# EcobitNRF9160.net
KiCad netlist of a schematic drawn in EAGLE
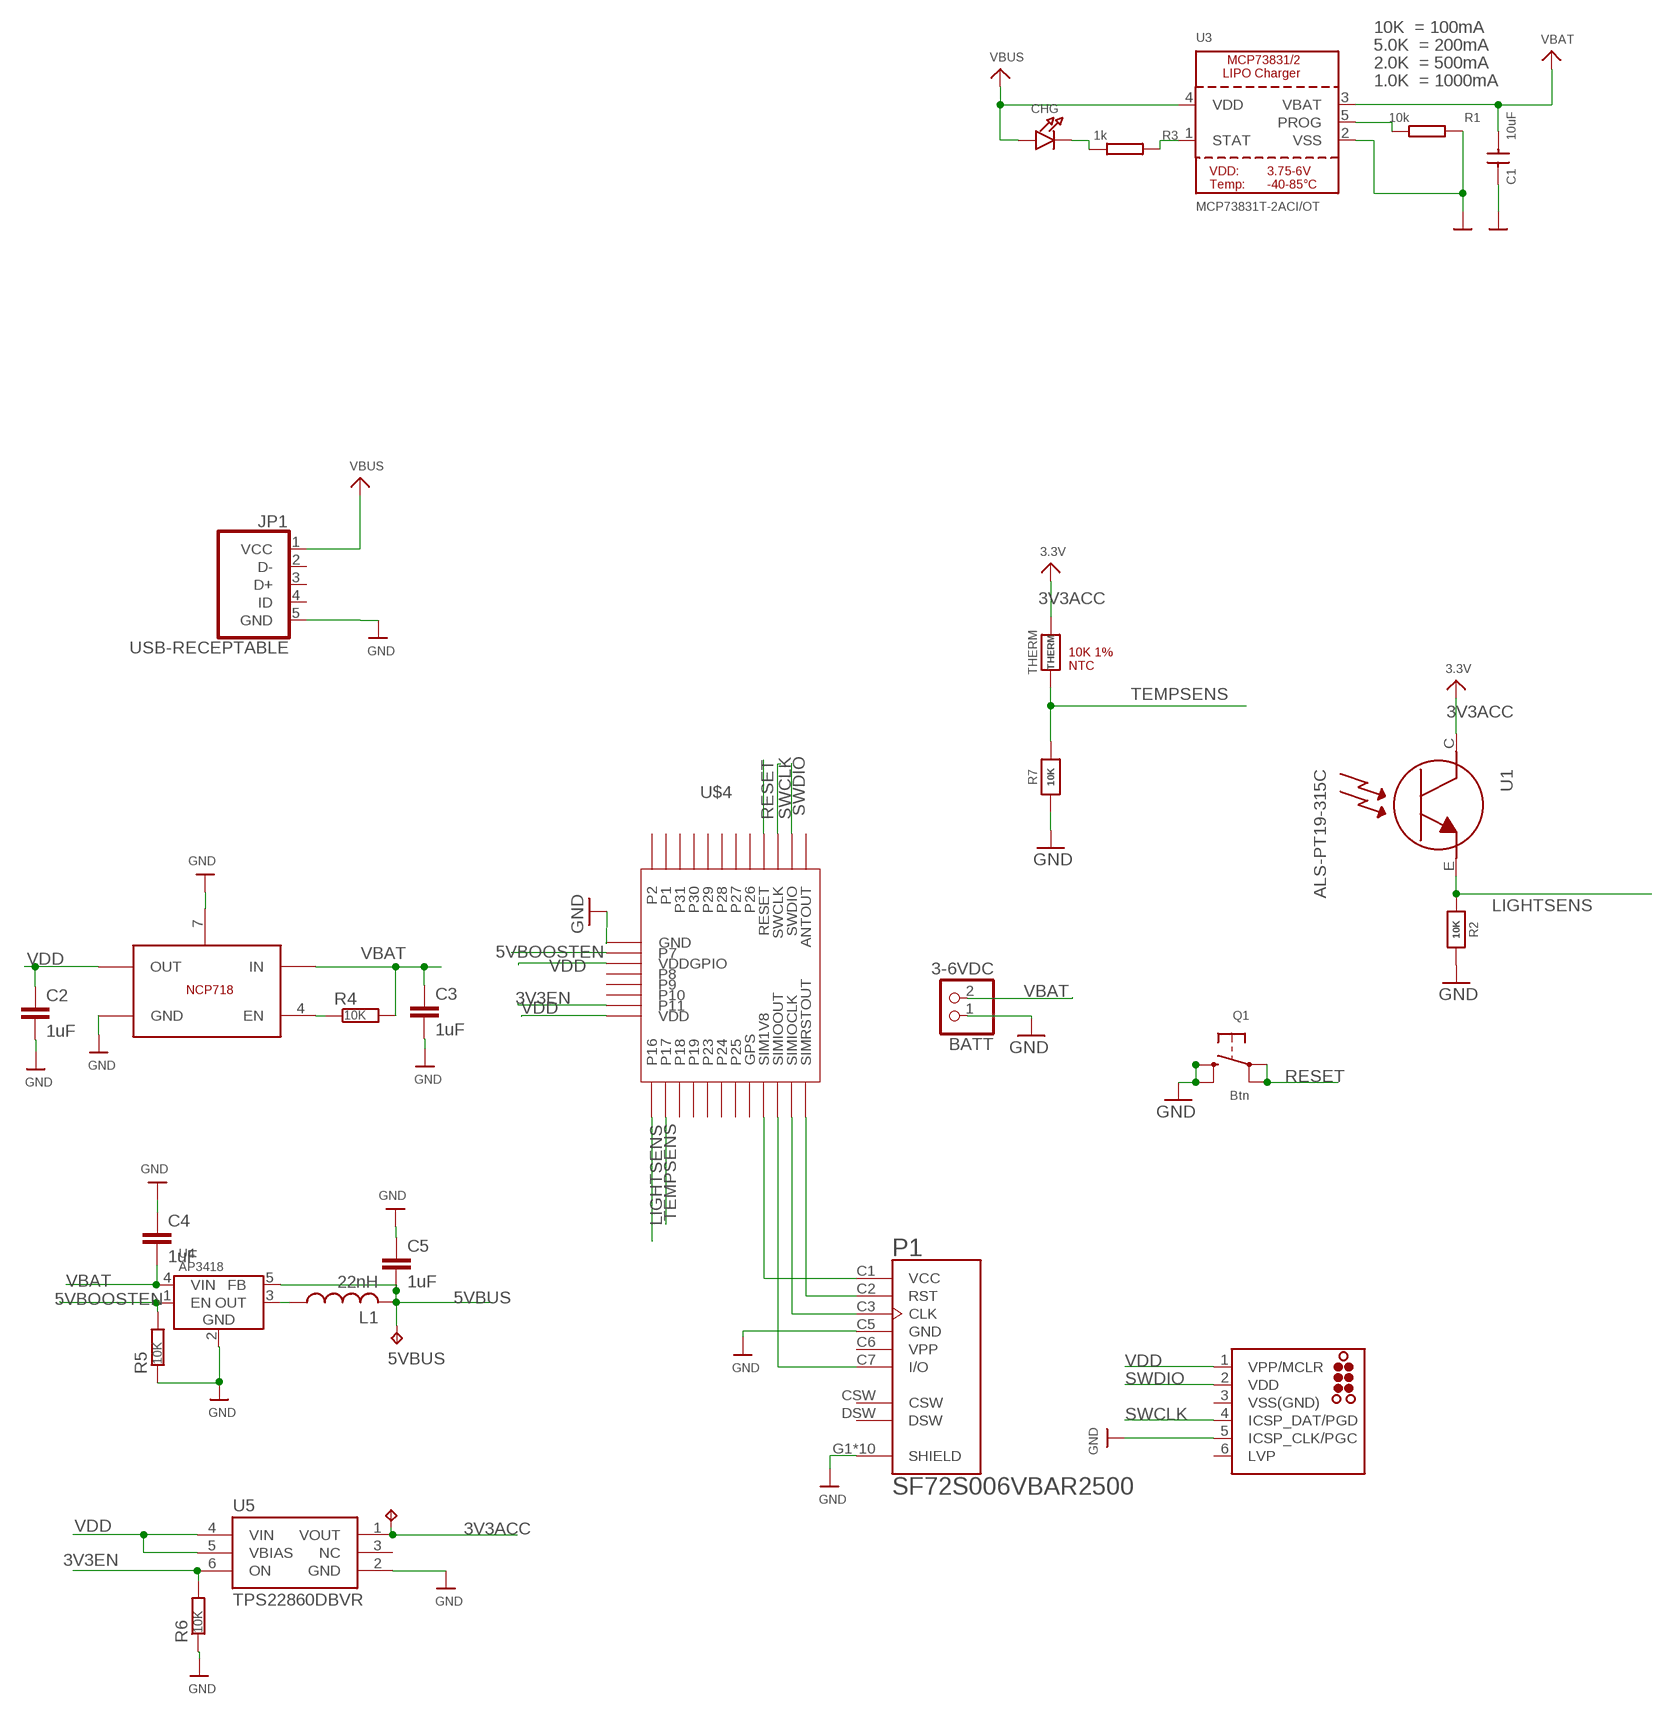
[diagram p0: schematic, sheet 1]

(export (version "E")
  (design (tool "Eeschema 10.0.6"))
  (components
    (comp (ref "5VBUS")
      (value "TPTP15R")
      (footprint "eagle-import:TP15R")
      (libsource (lib "eagle-import") (part "TPTP15R"))
    )
    (comp (ref "5VBUS1")
      (value "TPTP15R")
      (footprint "eagle-import:TP15R")
      (libsource (lib "eagle-import") (part "TPTP15R"))
    )
    (comp (ref "BATT")
      (value "3-6VDC")
      (footprint "eagle-import:JSTPH2")
      (libsource (lib "eagle-import") (part "CON_JST_PH_2PIN"))
    )
    (comp (ref "C1")
      (value "10uF")
      (footprint "eagle-import:C-0402")
      (libsource (lib "eagle-import") (part "CAP0402"))
    )
    (comp (ref "C2")
      (value "1uF")
      (footprint "eagle-import:RESC0402_N")
      (libsource (lib "eagle-import") (part "CAPACITOR_0402_N"))
    )
    (comp (ref "C3")
      (value "1uF")
      (footprint "eagle-import:RESC0402_N")
      (libsource (lib "eagle-import") (part "CAPACITOR_0402_N"))
    )
    (comp (ref "C4")
      (value "1uF")
      (footprint "eagle-import:RESC0402_N")
      (libsource (lib "eagle-import") (part "CAPACITOR_0402_N"))
    )
    (comp (ref "C5")
      (value "1uF")
      (footprint "eagle-import:RESC0402_N")
      (libsource (lib "eagle-import") (part "CAPACITOR_0402_N"))
    )
    (comp (ref "CHG")
      (value "LED0805_NOOUTLINE")
      (footprint "eagle-import:CHIPLED_0805_NOOUTLINE")
      (libsource (lib "eagle-import") (part "LED0805_NOOUTLINE"))
    )
    (comp (ref "J2")
      (value "TC2030-MCP-NL")
      (footprint "eagle-import:TC2030-MCP-NL")
      (libsource (lib "eagle-import") (part "TC2030-MCP-NL"))
    )
    (comp (ref "JP1")
      (value "USB-RECEPTABLE")
      (footprint "eagle-import:FCI-10103594-0001LF")
      (libsource (lib "eagle-import") (part "USB-RECEPTABLE"))
    )
    (comp (ref "L1")
      (value "22nH")
      (footprint "eagle-import:RESC0603_N")
      (libsource (lib "eagle-import") (part "INDUCTOR_0603_N"))
    )
    (comp (ref "P1")
      (value "SF72S006VBAR2500")
      (footprint "eagle-import:JAE_SF72S006VBAR2500")
      (fields (field (name "MF") "JAE Electronics"))
      (libsource (lib "eagle-import") (part "SF72S006VBAR2500"))
    )
    (comp (ref "Q1")
      (value "Btn")
      (footprint "eagle-import:BTN_KMR2_4.6X2.8")
      (libsource (lib "eagle-import") (part "SWITCH_TACT_SMT4.6X2.8"))
    )
    (comp (ref "R1")
      (value "10k")
      (footprint "eagle-import:R0402")
      (libsource (lib "eagle-import") (part "RESR0402"))
    )
    (comp (ref "R2")
      (value "10K")
      (footprint "eagle-import:0603-NO")
      (libsource (lib "eagle-import") (part "RESISTOR_0603_NOOUT"))
    )
    (comp (ref "R3")
      (value "1k")
      (footprint "eagle-import:R0402")
      (libsource (lib "eagle-import") (part "RESR0402"))
    )
    (comp (ref "R4")
      (value "10K")
      (footprint "eagle-import:RESC0402_N")
      (libsource (lib "eagle-import") (part "RESISTOR_0402_N"))
    )
    (comp (ref "R5")
      (value "10K")
      (footprint "eagle-import:RESC0402_N")
      (libsource (lib "eagle-import") (part "RESISTOR_0402_N"))
    )
    (comp (ref "R6")
      (value "10K")
      (footprint "eagle-import:RESC0402_N")
      (libsource (lib "eagle-import") (part "RESISTOR_0402_N"))
    )
    (comp (ref "R7")
      (value "10K")
      (footprint "eagle-import:0603-NO")
      (libsource (lib "eagle-import") (part "RESISTOR_0603_NOOUT"))
    )
    (comp (ref "THERM")
      (value "THERM")
      (footprint "eagle-import:_0402")
      (libsource (lib "eagle-import") (part "RESISTOR_0402"))
    )
    (comp (ref "U$4")
      (value "NRF9160MODULE")
      (footprint "eagle-import:NRF9160MODULE")
      (libsource (lib "eagle-import") (part "NRF9160MODULE"))
    )
    (comp (ref "U1")
      (value "ALS-PT19-315C")
      (footprint "eagle-import:ALS-PT19-315C")
      (libsource (lib "eagle-import") (part "LIGHT_ALS-PT19-315C"))
    )
    (comp (ref "U2")
      (value "NCP718")
      (footprint "eagle-import:NCP718-WDFN6")
      (libsource (lib "eagle-import") (part "NCP718"))
    )
    (comp (ref "U3")
      (value "MCP73831T-2ACI/OT")
      (footprint "eagle-import:SOT23-5")
      (libsource (lib "eagle-import") (part "MCP73831/2"))
    )
    (comp (ref "U4")
      (value "AP3418")
      (footprint "eagle-import:SOT25")
      (libsource (lib "eagle-import") (part "AP3418"))
    )
    (comp (ref "U5")
      (value "TPS22860DBVR")
      (footprint "eagle-import:R-PDSO-G6")
      (libsource (lib "eagle-import") (part "TPS22860DBVR"))
    )
  )
  (nets
    (net (code "1") (name "/3V3EN") (class "Default")
      (node (ref "R6") (pin "2") (pinfunction "2_2") (pintype "passive"))
      (node (ref "U$4") (pin "P11") (pinfunction "P11_P11") (pintype "bidirectional"))
      (node (ref "U5") (pin "6") (pinfunction "ON_6") (pintype "input"))
    )
    (net (code "2") (name "/5VBOOSTEN") (class "Default")
      (node (ref "R5") (pin "2") (pinfunction "2_2") (pintype "passive"))
      (node (ref "U$4") (pin "P7") (pinfunction "P7_P7") (pintype "bidirectional"))
      (node (ref "U4") (pin "1") (pinfunction "EN_1") (pintype "bidirectional"))
    )
    (net (code "3") (name "/5VBUS") (class "Default")
      (node (ref "5VBUS") (pin "TP") (pinfunction "TP_TP") (pintype "input"))
      (node (ref "C5") (pin "2") (pinfunction "2_2") (pintype "passive"))
      (node (ref "L1") (pin "2") (pinfunction "2_2") (pintype "passive"))
      (node (ref "U4") (pin "5") (pinfunction "FB_5") (pintype "bidirectional"))
    )
    (net (code "4") (name "/LIGHTSENS") (class "Default")
      (node (ref "R2") (pin "2") (pinfunction "2_2") (pintype "passive"))
      (node (ref "U$4") (pin "P16") (pinfunction "P16_P16") (pintype "bidirectional"))
      (node (ref "U1") (pin "E") (pinfunction "E_E") (pintype "bidirectional"))
    )
    (net (code "5") (name "/RESET") (class "Default")
      (node (ref "Q1") (pin "A") (pinfunction "P_A") (pintype "passive"))
      (node (ref "Q1") (pin "A'") (pinfunction "P1_A'") (pintype "passive"))
      (node (ref "U$4") (pin "RESET") (pinfunction "RESET_RESET") (pintype "bidirectional"))
    )
    (net (code "6") (name "/SWCLK") (class "Default")
      (node (ref "J2") (pin "4") (pinfunction "ICSP_DAT/PGD_4") (pintype "bidirectional"))
      (node (ref "U$4") (pin "SWCLK") (pinfunction "SWCLK_SWCLK") (pintype "bidirectional"))
    )
    (net (code "7") (name "/SWDIO") (class "Default")
      (node (ref "J2") (pin "2") (pinfunction "VDD_2") (pintype "power_in"))
      (node (ref "U$4") (pin "SWDIO") (pinfunction "SWDIO_SWDIO") (pintype "bidirectional"))
    )
    (net (code "8") (name "/TEMPSENS") (class "Default")
      (node (ref "R7") (pin "2") (pinfunction "2_2") (pintype "passive"))
      (node (ref "THERM") (pin "1") (pinfunction "1_1") (pintype "passive"))
      (node (ref "U$4") (pin "P17") (pinfunction "P17_P17") (pintype "bidirectional"))
    )
    (net (code "9") (name "/VDD") (class "Default")
      (node (ref "C2") (pin "1") (pinfunction "1_1") (pintype "passive"))
      (node (ref "J2") (pin "1") (pinfunction "VPP/MCLR_1") (pintype "passive"))
      (node (ref "U$4") (pin "VDD") (pinfunction "VDD_VDD") (pintype "bidirectional"))
      (node (ref "U$4") (pin "VDDGPIO") (pinfunction "VDDGPIO_VDDGPIO") (pintype "bidirectional"))
      (node (ref "U2") (pin "1") (pinfunction "OUT_1") (pintype "power_in"))
      (node (ref "U5") (pin "4") (pinfunction "VIN_4") (pintype "power_in"))
      (node (ref "U5") (pin "5") (pinfunction "VBIAS_5") (pintype "power_in"))
    )
    (net (code "10") (name "/VPP") (class "Default")
      (node (ref "P1") (pin "C6") (pinfunction "VPP_C6") (pintype "power_in"))
    )
    (net (code "11") (name "/VSS(GND)") (class "Default")
      (node (ref "J2") (pin "3") (pinfunction "VSS(GND)_3") (pintype "power_in"))
    )
    (net (code "12") (name "3.3V") (class "Default")
      (node (ref "5VBUS1") (pin "TP") (pinfunction "TP_TP") (pintype "input"))
      (node (ref "THERM") (pin "2") (pinfunction "2_2") (pintype "passive"))
      (node (ref "U1") (pin "C") (pinfunction "C_C") (pintype "bidirectional"))
      (node (ref "U5") (pin "1") (pinfunction "VOUT_1") (pintype "power_in"))
    )
    (net (code "13") (name "GND") (class "Default")
      (node (ref "BATT") (pin "1") (pinfunction "1_1") (pintype "passive"))
      (node (ref "C1") (pin "2") (pinfunction "2_2") (pintype "bidirectional"))
      (node (ref "C2") (pin "2") (pinfunction "2_2") (pintype "passive"))
      (node (ref "C3") (pin "2") (pinfunction "2_2") (pintype "passive"))
      (node (ref "C4") (pin "1") (pinfunction "1_1") (pintype "passive"))
      (node (ref "C5") (pin "1") (pinfunction "1_1") (pintype "passive"))
      (node (ref "J2") (pin "5") (pinfunction "ICSP_CLK/PGC_5") (pintype "output"))
      (node (ref "JP1") (pin "5") (pinfunction "GND_5") (pintype "bidirectional"))
      (node (ref "P1") (pin "C5") (pinfunction "GND_C5") (pintype "power_in"))
      (node (ref "P1") (pin "G1") (pinfunction "SHIELD_G1") (pintype "passive"))
      (node (ref "P1") (pin "G10") (pinfunction "SHIELD_G10") (pintype "passive"))
      (node (ref "P1") (pin "G2") (pinfunction "SHIELD_G2") (pintype "passive"))
      (node (ref "P1") (pin "G3") (pinfunction "SHIELD_G3") (pintype "passive"))
      (node (ref "P1") (pin "G4") (pinfunction "SHIELD_G4") (pintype "passive"))
      (node (ref "P1") (pin "G5") (pinfunction "SHIELD_G5") (pintype "passive"))
      (node (ref "P1") (pin "G6") (pinfunction "SHIELD_G6") (pintype "passive"))
      (node (ref "P1") (pin "G7") (pinfunction "SHIELD_G7") (pintype "passive"))
      (node (ref "P1") (pin "G8") (pinfunction "SHIELD_G8") (pintype "passive"))
      (node (ref "P1") (pin "G9") (pinfunction "SHIELD_G9") (pintype "passive"))
      (node (ref "Q1") (pin "B") (pinfunction "S_B") (pintype "passive"))
      (node (ref "Q1") (pin "B'") (pinfunction "S1_B'") (pintype "passive"))
      (node (ref "R1") (pin "1") (pinfunction "1_1") (pintype "bidirectional"))
      (node (ref "R2") (pin "1") (pinfunction "1_1") (pintype "passive"))
      (node (ref "R5") (pin "1") (pinfunction "1_1") (pintype "passive"))
      (node (ref "R6") (pin "1") (pinfunction "1_1") (pintype "passive"))
      (node (ref "R7") (pin "1") (pinfunction "1_1") (pintype "passive"))
      (node (ref "U$4") (pin "GND") (pinfunction "GND_GND") (pintype "bidirectional"))
      (node (ref "U2") (pin "3") (pinfunction "GND_3") (pintype "power_in"))
      (node (ref "U2") (pin "7") (pinfunction "GND_7") (pintype "power_in"))
      (node (ref "U3") (pin "2") (pinfunction "VSS_2") (pintype "power_in"))
      (node (ref "U4") (pin "2") (pinfunction "GND_2") (pintype "bidirectional"))
      (node (ref "U5") (pin "2") (pinfunction "GND_2") (pintype "power_in"))
    )
    (net (code "14") (name "Net-(CHG-PadC)") (class "Default")
      (node (ref "CHG") (pin "C") (pinfunction "C_C") (pintype "passive"))
      (node (ref "R3") (pin "2") (pinfunction "2_2") (pintype "bidirectional"))
    )
    (net (code "15") (name "Net-(P1-CLK)") (class "Default")
      (node (ref "P1") (pin "C3") (pinfunction "CLK_C3") (pintype "bidirectional"))
      (node (ref "U$4") (pin "SIMCLKOUT") (pinfunction "SIMIOCLK_SIMCLKOUT") (pintype "bidirectional"))
    )
    (net (code "16") (name "Net-(P1-I{slash}O)") (class "Default")
      (node (ref "P1") (pin "C7") (pinfunction "I/O_C7") (pintype "bidirectional"))
      (node (ref "U$4") (pin "SIMIOOUT") (pinfunction "SIMIOOUT_SIMIOOUT") (pintype "bidirectional"))
    )
    (net (code "17") (name "Net-(P1-RST)") (class "Default")
      (node (ref "P1") (pin "C2") (pinfunction "RST_C2") (pintype "bidirectional"))
      (node (ref "U$4") (pin "SIMRSTOUT") (pinfunction "SIMRSTOUT_SIMRSTOUT") (pintype "bidirectional"))
    )
    (net (code "18") (name "Net-(P1-VCC)") (class "Default")
      (node (ref "P1") (pin "C1") (pinfunction "VCC_C1") (pintype "power_in"))
      (node (ref "U$4") (pin "SIM1V8") (pinfunction "SIM1V8_SIM1V8") (pintype "bidirectional"))
    )
    (net (code "19") (name "Net-(U2-EN)") (class "Default")
      (node (ref "R4") (pin "1") (pinfunction "1_1") (pintype "passive"))
      (node (ref "U2") (pin "4") (pinfunction "EN_4") (pintype "bidirectional"))
    )
    (net (code "20") (name "Net-(U3-PROG)") (class "Default")
      (node (ref "R1") (pin "2") (pinfunction "2_2") (pintype "bidirectional"))
      (node (ref "U3") (pin "5") (pinfunction "PROG_5") (pintype "input"))
    )
    (net (code "21") (name "Net-(U3-STAT)") (class "Default")
      (node (ref "R3") (pin "1") (pinfunction "1_1") (pintype "bidirectional"))
      (node (ref "U3") (pin "1") (pinfunction "STAT_1") (pintype "output"))
    )
    (net (code "22") (name "Net-(U4-OUT)") (class "Default")
      (node (ref "L1") (pin "1") (pinfunction "1_1") (pintype "passive"))
      (node (ref "U4") (pin "3") (pinfunction "OUT_3") (pintype "bidirectional"))
    )
    (net (code "23") (name "VBAT") (class "Default")
      (node (ref "BATT") (pin "2") (pinfunction "2_2") (pintype "passive"))
      (node (ref "C1") (pin "1") (pinfunction "1_1") (pintype "bidirectional"))
      (node (ref "C3") (pin "1") (pinfunction "1_1") (pintype "passive"))
      (node (ref "C4") (pin "2") (pinfunction "2_2") (pintype "passive"))
      (node (ref "R4") (pin "2") (pinfunction "2_2") (pintype "passive"))
      (node (ref "U2") (pin "6") (pinfunction "IN_6") (pintype "power_in"))
      (node (ref "U3") (pin "3") (pinfunction "VBAT_3") (pintype "power_in"))
      (node (ref "U4") (pin "4") (pinfunction "VIN_4") (pintype "bidirectional"))
    )
    (net (code "24") (name "VBUS") (class "Default")
      (node (ref "CHG") (pin "A") (pinfunction "A_A") (pintype "passive"))
      (node (ref "JP1") (pin "1") (pinfunction "VCC_1") (pintype "bidirectional"))
      (node (ref "U3") (pin "4") (pinfunction "VDD_4") (pintype "power_in"))
    )
    (net (code "25") (name "unconnected-(J2-LVP-Pad6)") (class "Default")
      (node (ref "J2") (pin "6") (pinfunction "LVP_6") (pintype "bidirectional"))
    )
    (net (code "26") (name "unconnected-(JP1-D+-Pad3)") (class "Default")
      (node (ref "JP1") (pin "3") (pinfunction "D+_3") (pintype "bidirectional"))
    )
    (net (code "27") (name "unconnected-(JP1-D--Pad2)") (class "Default")
      (node (ref "JP1") (pin "2") (pinfunction "D-_2") (pintype "bidirectional"))
    )
    (net (code "28") (name "unconnected-(JP1-ID-Pad4)") (class "Default")
      (node (ref "JP1") (pin "4") (pinfunction "ID_4") (pintype "bidirectional"))
    )
    (net (code "29") (name "unconnected-(P1-PadCSW)") (class "Default")
      (node (ref "P1") (pin "CSW") (pinfunction "CSW_CSW") (pintype "bidirectional"))
    )
    (net (code "30") (name "unconnected-(P1-PadDSW)") (class "Default")
      (node (ref "P1") (pin "DSW") (pinfunction "DSW_DSW") (pintype "bidirectional"))
    )
    (net (code "31") (name "unconnected-(U$4-PadANTOUT)") (class "Default")
      (node (ref "U$4") (pin "ANTOUT") (pinfunction "ANTOUT_ANTOUT") (pintype "bidirectional"))
    )
    (net (code "32") (name "unconnected-(U$4-PadGPS)") (class "Default")
      (node (ref "U$4") (pin "GPS") (pinfunction "GPS_GPS") (pintype "bidirectional"))
    )
    (net (code "33") (name "unconnected-(U$4-PadP1)") (class "Default")
      (node (ref "U$4") (pin "P1") (pinfunction "P1_P1") (pintype "bidirectional"))
    )
    (net (code "34") (name "unconnected-(U$4-PadP2)") (class "Default")
      (node (ref "U$4") (pin "P2") (pinfunction "P2_P2") (pintype "bidirectional"))
    )
    (net (code "35") (name "unconnected-(U$4-PadP8)") (class "Default")
      (node (ref "U$4") (pin "P8") (pinfunction "P8_P8") (pintype "bidirectional"))
    )
    (net (code "36") (name "unconnected-(U$4-PadP9)") (class "Default")
      (node (ref "U$4") (pin "P9") (pinfunction "P9_P9") (pintype "bidirectional"))
    )
    (net (code "37") (name "unconnected-(U$4-PadP10)") (class "Default")
      (node (ref "U$4") (pin "P10") (pinfunction "P10_P10") (pintype "bidirectional"))
    )
    (net (code "38") (name "unconnected-(U$4-PadP18)") (class "Default")
      (node (ref "U$4") (pin "P18") (pinfunction "P18_P18") (pintype "bidirectional"))
    )
    (net (code "39") (name "unconnected-(U$4-PadP19)") (class "Default")
      (node (ref "U$4") (pin "P19") (pinfunction "P19_P19") (pintype "bidirectional"))
    )
    (net (code "40") (name "unconnected-(U$4-PadP23)") (class "Default")
      (node (ref "U$4") (pin "P23") (pinfunction "P23_P23") (pintype "bidirectional"))
    )
    (net (code "41") (name "unconnected-(U$4-PadP24)") (class "Default")
      (node (ref "U$4") (pin "P24") (pinfunction "P24_P24") (pintype "bidirectional"))
    )
    (net (code "42") (name "unconnected-(U$4-PadP25)") (class "Default")
      (node (ref "U$4") (pin "P25") (pinfunction "P25_P25") (pintype "bidirectional"))
    )
    (net (code "43") (name "unconnected-(U$4-PadP26)") (class "Default")
      (node (ref "U$4") (pin "P26") (pinfunction "P26_P26") (pintype "bidirectional"))
    )
    (net (code "44") (name "unconnected-(U$4-PadP27)") (class "Default")
      (node (ref "U$4") (pin "P27") (pinfunction "P27_P27") (pintype "bidirectional"))
    )
    (net (code "45") (name "unconnected-(U$4-PadP28)") (class "Default")
      (node (ref "U$4") (pin "P28") (pinfunction "P28_P28") (pintype "bidirectional"))
    )
    (net (code "46") (name "unconnected-(U$4-PadP29)") (class "Default")
      (node (ref "U$4") (pin "P29") (pinfunction "P29_P29") (pintype "bidirectional"))
    )
    (net (code "47") (name "unconnected-(U$4-PadP30)") (class "Default")
      (node (ref "U$4") (pin "P30") (pinfunction "P30_P30") (pintype "bidirectional"))
    )
    (net (code "48") (name "unconnected-(U$4-PadP31)") (class "Default")
      (node (ref "U$4") (pin "P31") (pinfunction "P31_P31") (pintype "bidirectional"))
    )
    (net (code "49") (name "unconnected-(U5-NC-Pad3)") (class "Default")
      (node (ref "U5") (pin "3") (pinfunction "NC_3") (pintype "no_connect"))
    )
  )
)
